# PMI_board.net
KiCad netlist of a schematic drawn in EAGLE
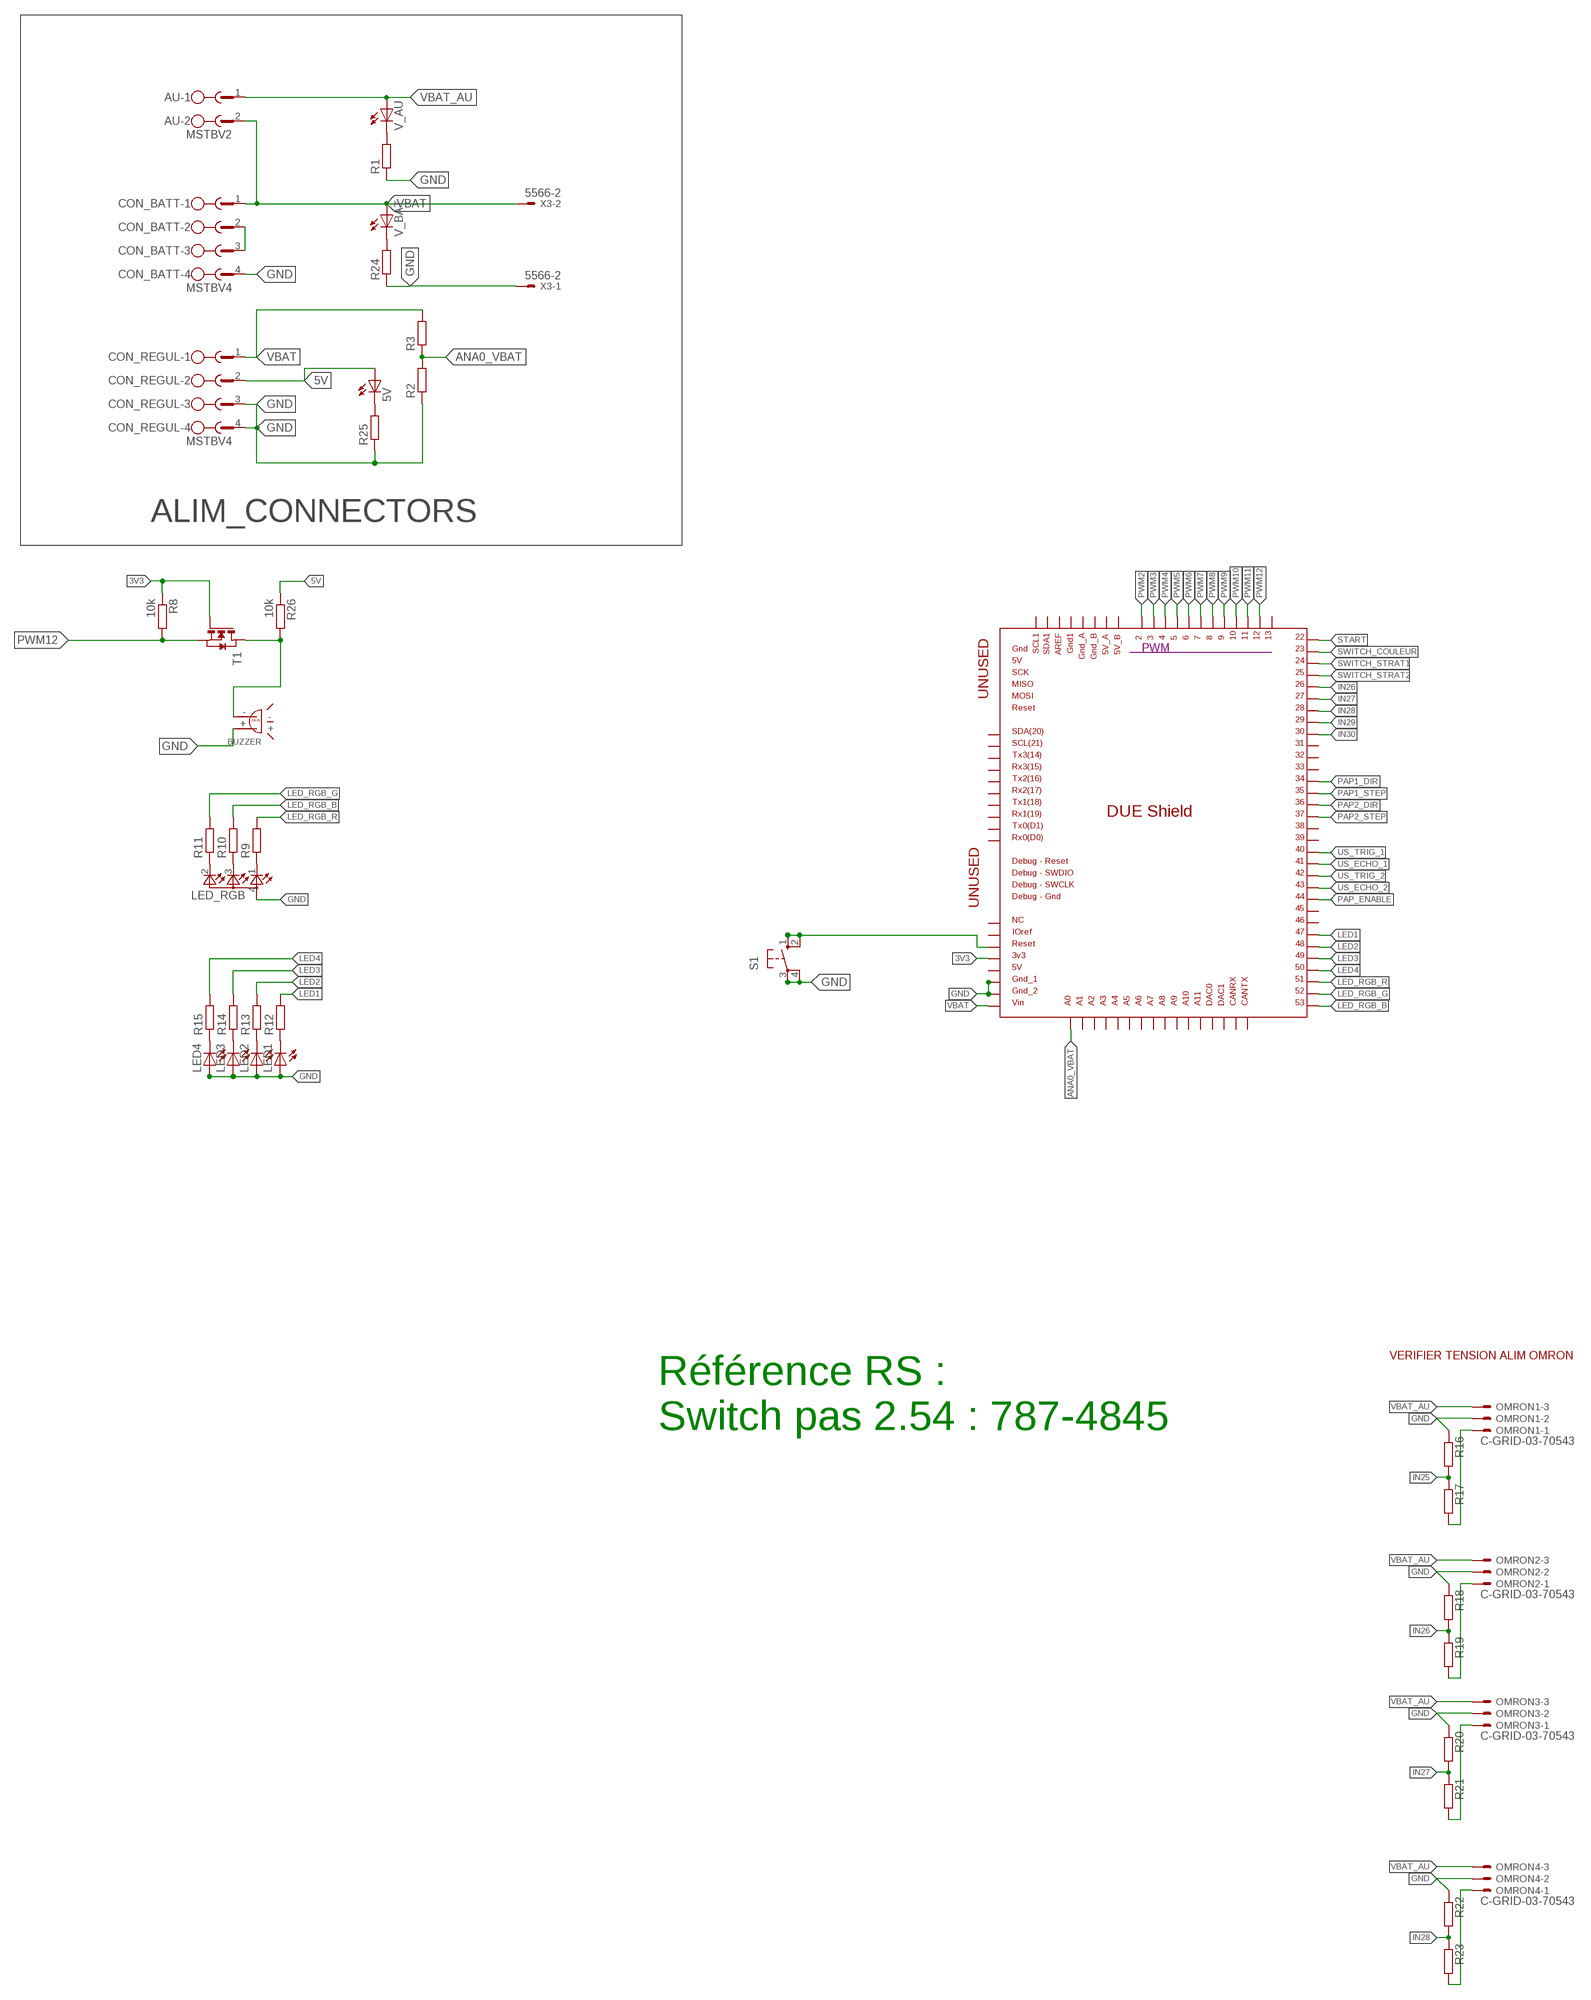
[diagram p0: schematic, sheet 1, part 1 of 2]
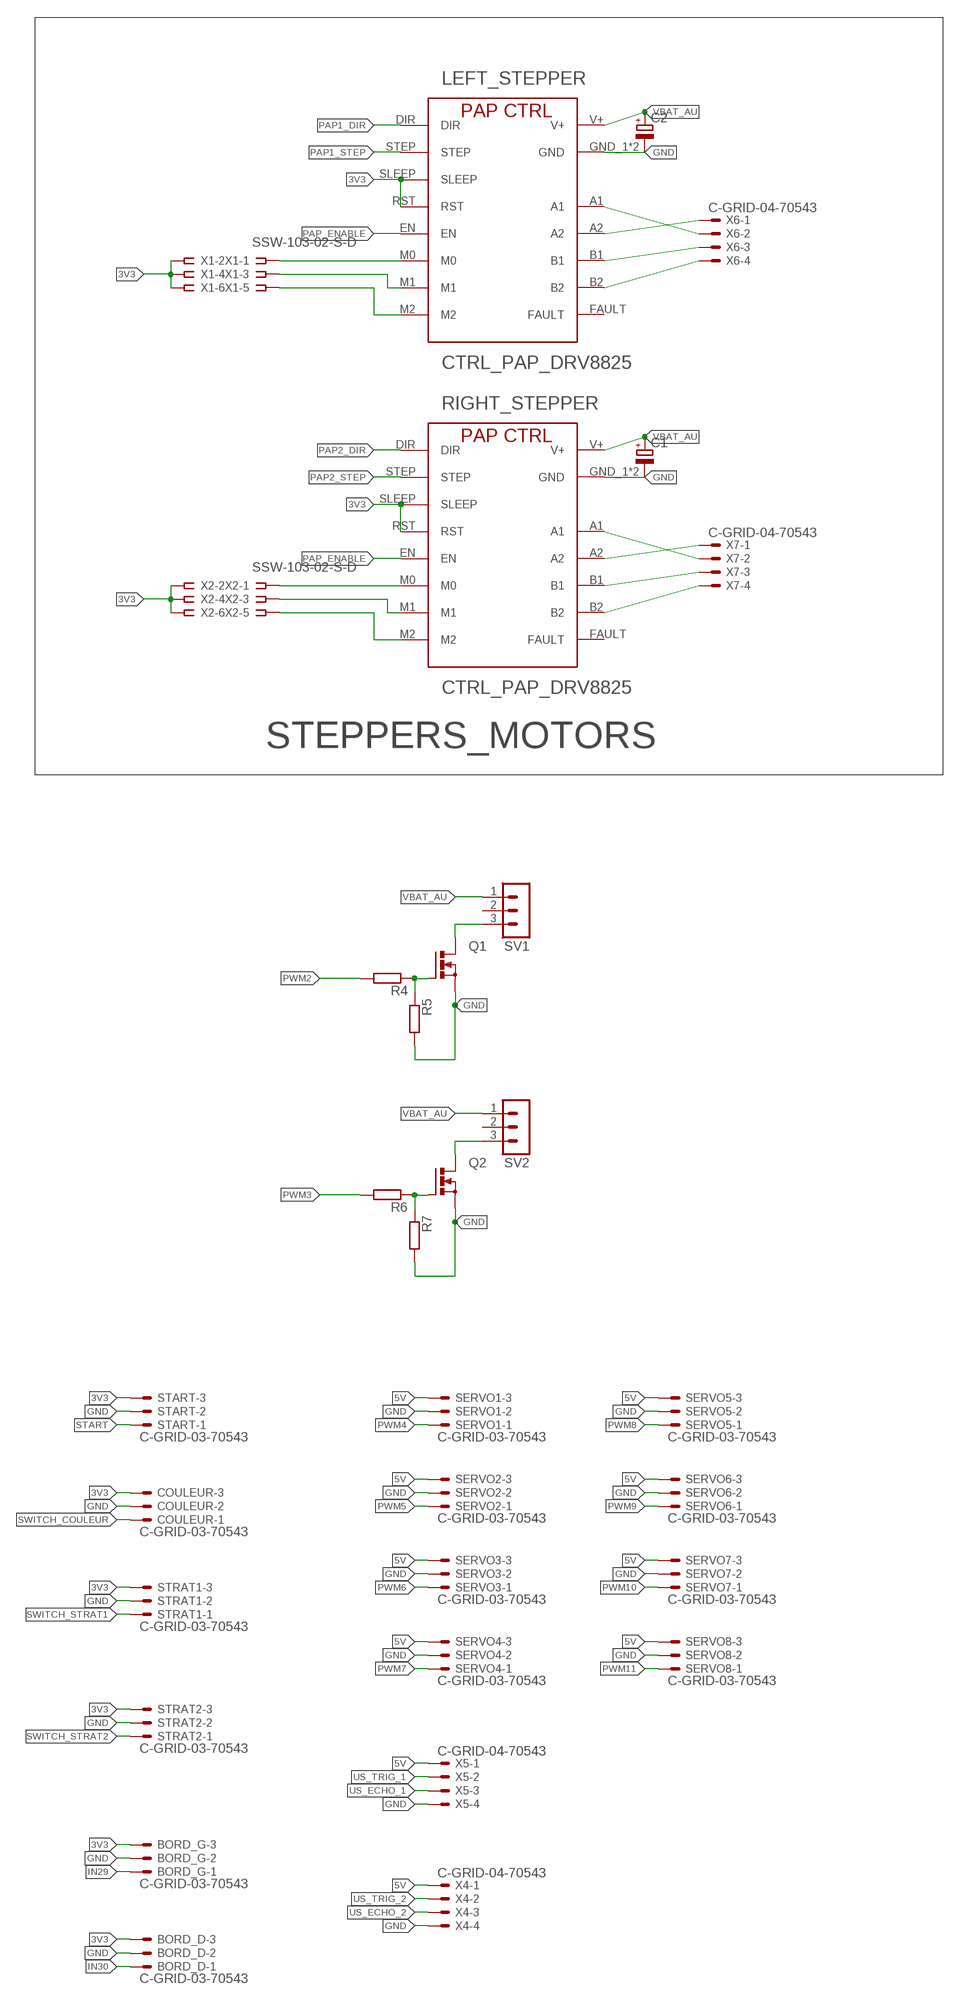
[diagram p1: schematic, sheet 1, part 2 of 2]

(export (version "E")
  (design (tool "Eeschema 10.0.6"))
  (components
    (comp (ref "5V")
      (value "LED5MM")
      (footprint "eagle-import:LED5MM")
      (libsource (lib "eagle-import") (part "LED5MM"))
    )
    (comp (ref "AU")
      (value "MSTBV2")
      (footprint "eagle-import:MSTBV2")
      (fields (field (name "MPN") "MSTBV 2,5/2-GF-5.08"))
      (libsource (lib "eagle-import") (part "MSTBV2"))
    )
    (comp (ref "BORD_D")
      (value "C-GRID-03-70543")
      (footprint "eagle-import:70543-03")
      (libsource (lib "eagle-import") (part "C-GRID-03-70543"))
    )
    (comp (ref "BORD_G")
      (value "C-GRID-03-70543")
      (footprint "eagle-import:70543-03")
      (libsource (lib "eagle-import") (part "C-GRID-03-70543"))
    )
    (comp (ref "BUZZER")
      (value "BUZZER")
      (footprint "eagle-import:BUZZER")
      (libsource (lib "eagle-import") (part "BUZZER"))
    )
    (comp (ref "C1")
      (value "CPOL-EUD")
      (footprint "eagle-import:PANASONIC_D")
      (libsource (lib "eagle-import") (part "CPOL-EUD"))
    )
    (comp (ref "C2")
      (value "CPOL-EUD")
      (footprint "eagle-import:PANASONIC_D")
      (libsource (lib "eagle-import") (part "CPOL-EUD"))
    )
    (comp (ref "CON_BATT")
      (value "MSTBV4")
      (footprint "eagle-import:MSTBV4")
      (fields (field (name "MPN") "MSTBV 2,5/4-GF-5.08"))
      (libsource (lib "eagle-import") (part "MSTBV4"))
    )
    (comp (ref "CON_REGUL")
      (value "MSTBV4")
      (footprint "eagle-import:MSTBV4")
      (fields (field (name "MPN") "MSTBV 2,5/4-GF-5.08"))
      (libsource (lib "eagle-import") (part "MSTBV4"))
    )
    (comp (ref "COULEUR")
      (value "C-GRID-03-70543")
      (footprint "eagle-import:70543-03")
      (libsource (lib "eagle-import") (part "C-GRID-03-70543"))
    )
    (comp (ref "LED1")
      (value "LED3MM")
      (footprint "eagle-import:LED3MM")
      (libsource (lib "eagle-import") (part "LED3MM"))
    )
    (comp (ref "LED2")
      (value "LED3MM")
      (footprint "eagle-import:LED3MM")
      (libsource (lib "eagle-import") (part "LED3MM"))
    )
    (comp (ref "LED3")
      (value "LED3MM")
      (footprint "eagle-import:LED3MM")
      (libsource (lib "eagle-import") (part "LED3MM"))
    )
    (comp (ref "LED4")
      (value "LED3MM")
      (footprint "eagle-import:LED3MM")
      (libsource (lib "eagle-import") (part "LED3MM"))
    )
    (comp (ref "LED_RGB")
      (value "TOPLED-3QPE_MAPPING")
      (footprint "eagle-import:P-LCC-4-3")
      (libsource (lib "eagle-import") (part "TOPLED-3QPE_MAPPING"))
    )
    (comp (ref "LEFT_STEPPER")
      (value "CTRL_PAP_DRV8825")
      (footprint "eagle-import:CTRL_PAP")
      (libsource (lib "eagle-import") (part "CTRL_PAP_DRV8825"))
    )
    (comp (ref "OMRON1")
      (value "C-GRID-03-70543")
      (footprint "eagle-import:70543-03")
      (libsource (lib "eagle-import") (part "C-GRID-03-70543"))
    )
    (comp (ref "OMRON2")
      (value "C-GRID-03-70543")
      (footprint "eagle-import:70543-03")
      (libsource (lib "eagle-import") (part "C-GRID-03-70543"))
    )
    (comp (ref "OMRON3")
      (value "C-GRID-03-70543")
      (footprint "eagle-import:70543-03")
      (libsource (lib "eagle-import") (part "C-GRID-03-70543"))
    )
    (comp (ref "OMRON4")
      (value "C-GRID-03-70543")
      (footprint "eagle-import:70543-03")
      (libsource (lib "eagle-import") (part "C-GRID-03-70543"))
    )
    (comp (ref "Q1")
      (value "PMOSFET_NTO220BV")
      (footprint "eagle-import:TO220BV")
      (libsource (lib "eagle-import") (part "PMOSFET_NTO220BV"))
    )
    (comp (ref "Q2")
      (value "PMOSFET_NTO220BV")
      (footprint "eagle-import:TO220BV")
      (libsource (lib "eagle-import") (part "PMOSFET_NTO220BV"))
    )
    (comp (ref "R1")
      (value "R-EU_M1206")
      (footprint "eagle-import:M1206")
      (libsource (lib "eagle-import") (part "R-EU_M1206"))
    )
    (comp (ref "R2")
      (value "R-EU_M1206")
      (footprint "eagle-import:M1206")
      (libsource (lib "eagle-import") (part "R-EU_M1206"))
    )
    (comp (ref "R3")
      (value "R-EU_M1206")
      (footprint "eagle-import:M1206")
      (libsource (lib "eagle-import") (part "R-EU_M1206"))
    )
    (comp (ref "R4")
      (value "R-EU_M1206")
      (footprint "eagle-import:M1206")
      (libsource (lib "eagle-import") (part "R-EU_M1206"))
    )
    (comp (ref "R5")
      (value "R-EU_M1206")
      (footprint "eagle-import:M1206")
      (libsource (lib "eagle-import") (part "R-EU_M1206"))
    )
    (comp (ref "R6")
      (value "R-EU_M1206")
      (footprint "eagle-import:M1206")
      (libsource (lib "eagle-import") (part "R-EU_M1206"))
    )
    (comp (ref "R7")
      (value "R-EU_M1206")
      (footprint "eagle-import:M1206")
      (libsource (lib "eagle-import") (part "R-EU_M1206"))
    )
    (comp (ref "R8")
      (value "10k")
      (footprint "eagle-import:M1206")
      (libsource (lib "eagle-import") (part "R-EU_M1206"))
    )
    (comp (ref "R9")
      (value "R-EU_M1206")
      (footprint "eagle-import:M1206")
      (libsource (lib "eagle-import") (part "R-EU_M1206"))
    )
    (comp (ref "R10")
      (value "R-EU_M1206")
      (footprint "eagle-import:M1206")
      (libsource (lib "eagle-import") (part "R-EU_M1206"))
    )
    (comp (ref "R11")
      (value "R-EU_M1206")
      (footprint "eagle-import:M1206")
      (libsource (lib "eagle-import") (part "R-EU_M1206"))
    )
    (comp (ref "R12")
      (value "R-EU_M1206")
      (footprint "eagle-import:M1206")
      (libsource (lib "eagle-import") (part "R-EU_M1206"))
    )
    (comp (ref "R13")
      (value "R-EU_M1206")
      (footprint "eagle-import:M1206")
      (libsource (lib "eagle-import") (part "R-EU_M1206"))
    )
    (comp (ref "R14")
      (value "R-EU_M1206")
      (footprint "eagle-import:M1206")
      (libsource (lib "eagle-import") (part "R-EU_M1206"))
    )
    (comp (ref "R15")
      (value "R-EU_M1206")
      (footprint "eagle-import:M1206")
      (libsource (lib "eagle-import") (part "R-EU_M1206"))
    )
    (comp (ref "R16")
      (value "R-EU_M1206")
      (footprint "eagle-import:M1206")
      (libsource (lib "eagle-import") (part "R-EU_M1206"))
    )
    (comp (ref "R17")
      (value "R-EU_M1206")
      (footprint "eagle-import:M1206")
      (libsource (lib "eagle-import") (part "R-EU_M1206"))
    )
    (comp (ref "R18")
      (value "R-EU_M1206")
      (footprint "eagle-import:M1206")
      (libsource (lib "eagle-import") (part "R-EU_M1206"))
    )
    (comp (ref "R19")
      (value "R-EU_M1206")
      (footprint "eagle-import:M1206")
      (libsource (lib "eagle-import") (part "R-EU_M1206"))
    )
    (comp (ref "R20")
      (value "R-EU_M1206")
      (footprint "eagle-import:M1206")
      (libsource (lib "eagle-import") (part "R-EU_M1206"))
    )
    (comp (ref "R21")
      (value "R-EU_M1206")
      (footprint "eagle-import:M1206")
      (libsource (lib "eagle-import") (part "R-EU_M1206"))
    )
    (comp (ref "R22")
      (value "R-EU_M1206")
      (footprint "eagle-import:M1206")
      (libsource (lib "eagle-import") (part "R-EU_M1206"))
    )
    (comp (ref "R23")
      (value "R-EU_M1206")
      (footprint "eagle-import:M1206")
      (libsource (lib "eagle-import") (part "R-EU_M1206"))
    )
    (comp (ref "R24")
      (value "R-EU_M1206")
      (footprint "eagle-import:M1206")
      (libsource (lib "eagle-import") (part "R-EU_M1206"))
    )
    (comp (ref "R25")
      (value "R-EU_M1206")
      (footprint "eagle-import:M1206")
      (libsource (lib "eagle-import") (part "R-EU_M1206"))
    )
    (comp (ref "R26")
      (value "10k")
      (footprint "eagle-import:M1206")
      (libsource (lib "eagle-import") (part "R-EU_M1206"))
    )
    (comp (ref "RIGHT_STEPPER")
      (value "CTRL_PAP_DRV8825")
      (footprint "eagle-import:CTRL_PAP")
      (libsource (lib "eagle-import") (part "CTRL_PAP_DRV8825"))
    )
    (comp (ref "S1")
      (value "10-XX")
      (footprint "eagle-import:B3F-10XX")
      (fields (field (name "MPN") "B3F-1000"))
      (libsource (lib "eagle-import") (part "10-XX"))
    )
    (comp (ref "SERVO1")
      (value "C-GRID-03-70543")
      (footprint "eagle-import:70543-03")
      (libsource (lib "eagle-import") (part "C-GRID-03-70543"))
    )
    (comp (ref "SERVO2")
      (value "C-GRID-03-70543")
      (footprint "eagle-import:70543-03")
      (libsource (lib "eagle-import") (part "C-GRID-03-70543"))
    )
    (comp (ref "SERVO3")
      (value "C-GRID-03-70543")
      (footprint "eagle-import:70543-03")
      (libsource (lib "eagle-import") (part "C-GRID-03-70543"))
    )
    (comp (ref "SERVO4")
      (value "C-GRID-03-70543")
      (footprint "eagle-import:70543-03")
      (libsource (lib "eagle-import") (part "C-GRID-03-70543"))
    )
    (comp (ref "SERVO5")
      (value "C-GRID-03-70543")
      (footprint "eagle-import:70543-03")
      (libsource (lib "eagle-import") (part "C-GRID-03-70543"))
    )
    (comp (ref "SERVO6")
      (value "C-GRID-03-70543")
      (footprint "eagle-import:70543-03")
      (libsource (lib "eagle-import") (part "C-GRID-03-70543"))
    )
    (comp (ref "SERVO7")
      (value "C-GRID-03-70543")
      (footprint "eagle-import:70543-03")
      (libsource (lib "eagle-import") (part "C-GRID-03-70543"))
    )
    (comp (ref "SERVO8")
      (value "C-GRID-03-70543")
      (footprint "eagle-import:70543-03")
      (libsource (lib "eagle-import") (part "C-GRID-03-70543"))
    )
    (comp (ref "START")
      (value "C-GRID-03-70543")
      (footprint "eagle-import:70543-03")
      (libsource (lib "eagle-import") (part "C-GRID-03-70543"))
    )
    (comp (ref "STRAT1")
      (value "C-GRID-03-70543")
      (footprint "eagle-import:70543-03")
      (libsource (lib "eagle-import") (part "C-GRID-03-70543"))
    )
    (comp (ref "STRAT2")
      (value "C-GRID-03-70543")
      (footprint "eagle-import:70543-03")
      (libsource (lib "eagle-import") (part "C-GRID-03-70543"))
    )
    (comp (ref "SV1")
      (value "MA03-1")
      (footprint "eagle-import:MA03-1")
      (libsource (lib "eagle-import") (part "MA03-1"))
    )
    (comp (ref "SV2")
      (value "MA03-1")
      (footprint "eagle-import:MA03-1")
      (libsource (lib "eagle-import") (part "MA03-1"))
    )
    (comp (ref "T1")
      (value "NMOSSOT23")
      (footprint "eagle-import:SOT-23")
      (libsource (lib "eagle-import") (part "NMOSSOT23"))
    )
    (comp (ref "U$1")
      (value "DUE(NORMAL)")
      (footprint "eagle-import:DUE(NORMAL)")
      (libsource (lib "eagle-import") (part "DUE(NORMAL)"))
    )
    (comp (ref "V_AU")
      (value "LED5MM")
      (footprint "eagle-import:LED5MM")
      (libsource (lib "eagle-import") (part "LED5MM"))
    )
    (comp (ref "V_BAT")
      (value "LED5MM")
      (footprint "eagle-import:LED5MM")
      (libsource (lib "eagle-import") (part "LED5MM"))
    )
    (comp (ref "X1")
      (value "SSW-103-02-S-D")
      (footprint "eagle-import:SSW-103-02-S-D")
      (libsource (lib "eagle-import") (part "SSW-103-02-S-D"))
    )
    (comp (ref "X2")
      (value "SSW-103-02-S-D")
      (footprint "eagle-import:SSW-103-02-S-D")
      (libsource (lib "eagle-import") (part "SSW-103-02-S-D"))
    )
    (comp (ref "X3")
      (value "5566-2")
      (footprint "eagle-import:5566-2")
      (libsource (lib "eagle-import") (part "5566-2"))
    )
    (comp (ref "X4")
      (value "C-GRID-04-70543")
      (footprint "eagle-import:70543-04")
      (libsource (lib "eagle-import") (part "C-GRID-04-70543"))
    )
    (comp (ref "X5")
      (value "C-GRID-04-70543")
      (footprint "eagle-import:70543-04")
      (libsource (lib "eagle-import") (part "C-GRID-04-70543"))
    )
    (comp (ref "X6")
      (value "C-GRID-04-70543")
      (footprint "eagle-import:70543-04")
      (libsource (lib "eagle-import") (part "C-GRID-04-70543"))
    )
    (comp (ref "X7")
      (value "C-GRID-04-70543")
      (footprint "eagle-import:70543-04")
      (libsource (lib "eagle-import") (part "C-GRID-04-70543"))
    )
  )
  (nets
    (net (code "1") (name "3V3") (class "Default")
      (node (ref "BORD_D") (pin "3") (pinfunction "S_3") (pintype "passive"))
      (node (ref "BORD_G") (pin "3") (pinfunction "S_3") (pintype "passive"))
      (node (ref "COULEUR") (pin "3") (pinfunction "S_3") (pintype "passive"))
      (node (ref "LEFT_STEPPER") (pin "RST") (pinfunction "RST_RST") (pintype "bidirectional"))
      (node (ref "LEFT_STEPPER") (pin "SLEEP") (pinfunction "SLEEP_SLEEP") (pintype "bidirectional"))
      (node (ref "R8") (pin "1") (pinfunction "1_1") (pintype "passive"))
      (node (ref "RIGHT_STEPPER") (pin "RST") (pinfunction "RST_RST") (pintype "bidirectional"))
      (node (ref "RIGHT_STEPPER") (pin "SLEEP") (pinfunction "SLEEP_SLEEP") (pintype "bidirectional"))
      (node (ref "START") (pin "3") (pinfunction "S_3") (pintype "passive"))
      (node (ref "STRAT1") (pin "3") (pinfunction "S_3") (pintype "passive"))
      (node (ref "STRAT2") (pin "3") (pinfunction "S_3") (pintype "passive"))
      (node (ref "T1") (pin "3") (pinfunction "G_3") (pintype "passive"))
      (node (ref "U$1") (pin "3V3") (pinfunction "3V3_3V3") (pintype "bidirectional"))
      (node (ref "X1") (pin "2") (pinfunction "1_2") (pintype "passive"))
      (node (ref "X1") (pin "4") (pinfunction "1_4") (pintype "passive"))
      (node (ref "X1") (pin "6") (pinfunction "1_6") (pintype "passive"))
      (node (ref "X2") (pin "2") (pinfunction "1_2") (pintype "passive"))
      (node (ref "X2") (pin "4") (pinfunction "1_4") (pintype "passive"))
      (node (ref "X2") (pin "6") (pinfunction "1_6") (pintype "passive"))
    )
    (net (code "2") (name "5V") (class "Default")
      (node (ref "5V") (pin "A") (pinfunction "A_A") (pintype "passive"))
      (node (ref "CON_REGUL") (pin "2") (pinfunction "1_2") (pintype "passive"))
      (node (ref "R26") (pin "1") (pinfunction "1_1") (pintype "passive"))
      (node (ref "SERVO1") (pin "3") (pinfunction "S_3") (pintype "passive"))
      (node (ref "SERVO2") (pin "3") (pinfunction "S_3") (pintype "passive"))
      (node (ref "SERVO3") (pin "3") (pinfunction "S_3") (pintype "passive"))
      (node (ref "SERVO4") (pin "3") (pinfunction "S_3") (pintype "passive"))
      (node (ref "SERVO5") (pin "3") (pinfunction "S_3") (pintype "passive"))
      (node (ref "SERVO6") (pin "3") (pinfunction "S_3") (pintype "passive"))
      (node (ref "SERVO7") (pin "3") (pinfunction "S_3") (pintype "passive"))
      (node (ref "SERVO8") (pin "3") (pinfunction "S_3") (pintype "passive"))
      (node (ref "X4") (pin "1") (pinfunction "S_1") (pintype "passive"))
      (node (ref "X5") (pin "1") (pinfunction "S_1") (pintype "passive"))
    )
    (net (code "3") (name "ANA0_VBAT") (class "Default")
      (node (ref "R2") (pin "2") (pinfunction "2_2") (pintype "passive"))
      (node (ref "R3") (pin "1") (pinfunction "1_1") (pintype "passive"))
      (node (ref "U$1") (pin "A0") (pinfunction "A0_A0") (pintype "bidirectional"))
    )
    (net (code "4") (name "GND") (class "Default")
      (node (ref "BORD_D") (pin "2") (pinfunction "S_2") (pintype "passive"))
      (node (ref "BORD_G") (pin "2") (pinfunction "S_2") (pintype "passive"))
      (node (ref "BUZZER") (pin "+") (pinfunction "+_+") (pintype "bidirectional"))
      (node (ref "C1") (pin "-") (pinfunction "-_-") (pintype "passive"))
      (node (ref "C2") (pin "-") (pinfunction "-_-") (pintype "passive"))
      (node (ref "CON_BATT") (pin "4") (pinfunction "1_4") (pintype "passive"))
      (node (ref "CON_REGUL") (pin "3") (pinfunction "1_3") (pintype "passive"))
      (node (ref "CON_REGUL") (pin "4") (pinfunction "1_4") (pintype "passive"))
      (node (ref "COULEUR") (pin "2") (pinfunction "S_2") (pintype "passive"))
      (node (ref "LED1") (pin "A") (pinfunction "A_A") (pintype "passive"))
      (node (ref "LED2") (pin "A") (pinfunction "A_A") (pintype "passive"))
      (node (ref "LED3") (pin "A") (pinfunction "A_A") (pintype "passive"))
      (node (ref "LED4") (pin "A") (pinfunction "A_A") (pintype "passive"))
      (node (ref "LED_RGB") (pin "4") (pinfunction "A2_4") (pintype "passive"))
      (node (ref "LEFT_STEPPER") (pin "GND_1") (pinfunction "GND_GND_1") (pintype "bidirectional"))
      (node (ref "LEFT_STEPPER") (pin "GND_2") (pinfunction "GND_GND_2") (pintype "bidirectional"))
      (node (ref "OMRON1") (pin "2") (pinfunction "S_2") (pintype "passive"))
      (node (ref "OMRON2") (pin "2") (pinfunction "S_2") (pintype "passive"))
      (node (ref "OMRON3") (pin "2") (pinfunction "S_2") (pintype "passive"))
      (node (ref "OMRON4") (pin "2") (pinfunction "S_2") (pintype "passive"))
      (node (ref "Q1") (pin "S") (pinfunction "S_S") (pintype "passive"))
      (node (ref "Q2") (pin "S") (pinfunction "S_S") (pintype "passive"))
      (node (ref "R1") (pin "1") (pinfunction "1_1") (pintype "passive"))
      (node (ref "R16") (pin "1") (pinfunction "1_1") (pintype "passive"))
      (node (ref "R18") (pin "1") (pinfunction "1_1") (pintype "passive"))
      (node (ref "R2") (pin "1") (pinfunction "1_1") (pintype "passive"))
      (node (ref "R20") (pin "1") (pinfunction "1_1") (pintype "passive"))
      (node (ref "R22") (pin "1") (pinfunction "1_1") (pintype "passive"))
      (node (ref "R24") (pin "1") (pinfunction "1_1") (pintype "passive"))
      (node (ref "R25") (pin "1") (pinfunction "1_1") (pintype "passive"))
      (node (ref "R5") (pin "2") (pinfunction "2_2") (pintype "passive"))
      (node (ref "R7") (pin "2") (pinfunction "2_2") (pintype "passive"))
      (node (ref "RIGHT_STEPPER") (pin "GND_1") (pinfunction "GND_GND_1") (pintype "bidirectional"))
      (node (ref "RIGHT_STEPPER") (pin "GND_2") (pinfunction "GND_GND_2") (pintype "bidirectional"))
      (node (ref "S1") (pin "3") (pinfunction "P_3") (pintype "passive"))
      (node (ref "S1") (pin "4") (pinfunction "P1_4") (pintype "passive"))
      (node (ref "SERVO1") (pin "2") (pinfunction "S_2") (pintype "passive"))
      (node (ref "SERVO2") (pin "2") (pinfunction "S_2") (pintype "passive"))
      (node (ref "SERVO3") (pin "2") (pinfunction "S_2") (pintype "passive"))
      (node (ref "SERVO4") (pin "2") (pinfunction "S_2") (pintype "passive"))
      (node (ref "SERVO5") (pin "2") (pinfunction "S_2") (pintype "passive"))
      (node (ref "SERVO6") (pin "2") (pinfunction "S_2") (pintype "passive"))
      (node (ref "SERVO7") (pin "2") (pinfunction "S_2") (pintype "passive"))
      (node (ref "SERVO8") (pin "2") (pinfunction "S_2") (pintype "passive"))
      (node (ref "START") (pin "2") (pinfunction "S_2") (pintype "passive"))
      (node (ref "STRAT1") (pin "2") (pinfunction "S_2") (pintype "passive"))
      (node (ref "STRAT2") (pin "2") (pinfunction "S_2") (pintype "passive"))
      (node (ref "U$1") (pin "GND_1") (pinfunction "GND_1_GND_1") (pintype "bidirectional"))
      (node (ref "U$1") (pin "GND_2") (pinfunction "GND_2_GND_2") (pintype "bidirectional"))
      (node (ref "X3") (pin "1") (pinfunction "S_1") (pintype "passive"))
      (node (ref "X4") (pin "4") (pinfunction "S_4") (pintype "passive"))
      (node (ref "X5") (pin "4") (pinfunction "S_4") (pintype "passive"))
    )
    (net (code "5") (name "IN25") (class "Default")
      (node (ref "R16") (pin "2") (pinfunction "2_2") (pintype "passive"))
      (node (ref "R17") (pin "1") (pinfunction "1_1") (pintype "passive"))
    )
    (net (code "6") (name "IN26") (class "Default")
      (node (ref "R18") (pin "2") (pinfunction "2_2") (pintype "passive"))
      (node (ref "R19") (pin "1") (pinfunction "1_1") (pintype "passive"))
      (node (ref "U$1") (pin "26") (pinfunction "26_26") (pintype "bidirectional"))
    )
    (net (code "7") (name "IN27") (class "Default")
      (node (ref "R20") (pin "2") (pinfunction "2_2") (pintype "passive"))
      (node (ref "R21") (pin "1") (pinfunction "1_1") (pintype "passive"))
      (node (ref "U$1") (pin "27") (pinfunction "27_27") (pintype "bidirectional"))
    )
    (net (code "8") (name "IN28") (class "Default")
      (node (ref "R22") (pin "2") (pinfunction "2_2") (pintype "passive"))
      (node (ref "R23") (pin "1") (pinfunction "1_1") (pintype "passive"))
      (node (ref "U$1") (pin "28") (pinfunction "28_28") (pintype "bidirectional"))
    )
    (net (code "9") (name "IN29") (class "Default")
      (node (ref "BORD_G") (pin "1") (pinfunction "S_1") (pintype "passive"))
      (node (ref "U$1") (pin "29") (pinfunction "29_29") (pintype "bidirectional"))
    )
    (net (code "10") (name "IN30") (class "Default")
      (node (ref "BORD_D") (pin "1") (pinfunction "S_1") (pintype "passive"))
      (node (ref "U$1") (pin "30") (pinfunction "30_30") (pintype "bidirectional"))
    )
    (net (code "11") (name "LED1") (class "Default")
      (node (ref "R12") (pin "2") (pinfunction "2_2") (pintype "passive"))
      (node (ref "U$1") (pin "47") (pinfunction "47_47") (pintype "bidirectional"))
    )
    (net (code "12") (name "LED2") (class "Default")
      (node (ref "R13") (pin "2") (pinfunction "2_2") (pintype "passive"))
      (node (ref "U$1") (pin "48") (pinfunction "48_48") (pintype "bidirectional"))
    )
    (net (code "13") (name "LED3") (class "Default")
      (node (ref "R14") (pin "2") (pinfunction "2_2") (pintype "passive"))
      (node (ref "U$1") (pin "49") (pinfunction "49_49") (pintype "bidirectional"))
    )
    (net (code "14") (name "LED4") (class "Default")
      (node (ref "R15") (pin "2") (pinfunction "2_2") (pintype "passive"))
      (node (ref "U$1") (pin "50") (pinfunction "50_50") (pintype "bidirectional"))
    )
    (net (code "15") (name "LED_RGB_B") (class "Default")
      (node (ref "R10") (pin "2") (pinfunction "2_2") (pintype "passive"))
      (node (ref "U$1") (pin "53") (pinfunction "53_53") (pintype "bidirectional"))
    )
    (net (code "16") (name "LED_RGB_G") (class "Default")
      (node (ref "R11") (pin "2") (pinfunction "2_2") (pintype "passive"))
      (node (ref "U$1") (pin "52") (pinfunction "52_52") (pintype "bidirectional"))
    )
    (net (code "17") (name "LED_RGB_R") (class "Default")
      (node (ref "R9") (pin "2") (pinfunction "2_2") (pintype "passive"))
      (node (ref "U$1") (pin "51") (pinfunction "51_51") (pintype "bidirectional"))
    )
    (net (code "18") (name "Net-(5V-C)") (class "Default")
      (node (ref "5V") (pin "K") (pinfunction "C_K") (pintype "passive"))
      (node (ref "R25") (pin "2") (pinfunction "2_2") (pintype "passive"))
    )
    (net (code "19") (name "Net-(CON_BATTB-1)") (class "Default")
      (node (ref "CON_BATT") (pin "2") (pinfunction "1_2") (pintype "passive"))
      (node (ref "CON_BATT") (pin "3") (pinfunction "1_3") (pintype "passive"))
    )
    (net (code "20") (name "Net-(LED1-C)") (class "Default")
      (node (ref "LED1") (pin "K") (pinfunction "C_K") (pintype "passive"))
      (node (ref "R12") (pin "1") (pinfunction "1_1") (pintype "passive"))
    )
    (net (code "21") (name "Net-(LED2-C)") (class "Default")
      (node (ref "LED2") (pin "K") (pinfunction "C_K") (pintype "passive"))
      (node (ref "R13") (pin "1") (pinfunction "1_1") (pintype "passive"))
    )
    (net (code "22") (name "Net-(LED3-C)") (class "Default")
      (node (ref "LED3") (pin "K") (pinfunction "C_K") (pintype "passive"))
      (node (ref "R14") (pin "1") (pinfunction "1_1") (pintype "passive"))
    )
    (net (code "23") (name "Net-(LED4-C)") (class "Default")
      (node (ref "LED4") (pin "K") (pinfunction "C_K") (pintype "passive"))
      (node (ref "R15") (pin "1") (pinfunction "1_1") (pintype "passive"))
    )
    (net (code "24") (name "Net-(LED_RGB-CBLUE)") (class "Default")
      (node (ref "LED_RGB") (pin "3") (pinfunction "CBLUE_3") (pintype "passive"))
      (node (ref "R10") (pin "1") (pinfunction "1_1") (pintype "passive"))
    )
    (net (code "25") (name "Net-(LED_RGB-CGREEN)") (class "Default")
      (node (ref "LED_RGB") (pin "2") (pinfunction "CGREEN_2") (pintype "passive"))
      (node (ref "R11") (pin "1") (pinfunction "1_1") (pintype "passive"))
    )
    (net (code "26") (name "Net-(LED_RGB-CRED)") (class "Default")
      (node (ref "LED_RGB") (pin "1") (pinfunction "CRED_1") (pintype "passive"))
      (node (ref "R9") (pin "1") (pinfunction "1_1") (pintype "passive"))
    )
    (net (code "27") (name "Net-(LEFT_STEPPER-PadM0)") (class "Default")
      (node (ref "LEFT_STEPPER") (pin "M0") (pinfunction "M0_M0") (pintype "bidirectional"))
      (node (ref "X1") (pin "1") (pinfunction "1_1") (pintype "passive"))
    )
    (net (code "28") (name "Net-(OMRON1A-S)") (class "Default")
      (node (ref "OMRON1") (pin "1") (pinfunction "S_1") (pintype "passive"))
      (node (ref "R17") (pin "2") (pinfunction "2_2") (pintype "passive"))
    )
    (net (code "29") (name "Net-(OMRON2A-S)") (class "Default")
      (node (ref "OMRON2") (pin "1") (pinfunction "S_1") (pintype "passive"))
      (node (ref "R19") (pin "2") (pinfunction "2_2") (pintype "passive"))
    )
    (net (code "30") (name "Net-(OMRON3A-S)") (class "Default")
      (node (ref "OMRON3") (pin "1") (pinfunction "S_1") (pintype "passive"))
      (node (ref "R21") (pin "2") (pinfunction "2_2") (pintype "passive"))
    )
    (net (code "31") (name "Net-(OMRON4A-S)") (class "Default")
      (node (ref "OMRON4") (pin "1") (pinfunction "S_1") (pintype "passive"))
      (node (ref "R23") (pin "2") (pinfunction "2_2") (pintype "passive"))
    )
    (net (code "32") (name "Net-(Q1-PadD)") (class "Default")
      (node (ref "Q1") (pin "D") (pinfunction "D_D") (pintype "passive"))
      (node (ref "SV1") (pin "3") (pinfunction "3_3") (pintype "passive"))
    )
    (net (code "33") (name "Net-(Q1-PadG)") (class "Default")
      (node (ref "Q1") (pin "G") (pinfunction "G_G") (pintype "passive"))
      (node (ref "R4") (pin "1") (pinfunction "1_1") (pintype "passive"))
      (node (ref "R5") (pin "1") (pinfunction "1_1") (pintype "passive"))
    )
    (net (code "34") (name "Net-(Q2-PadD)") (class "Default")
      (node (ref "Q2") (pin "D") (pinfunction "D_D") (pintype "passive"))
      (node (ref "SV2") (pin "3") (pinfunction "3_3") (pintype "passive"))
    )
    (net (code "35") (name "Net-(Q2-PadG)") (class "Default")
      (node (ref "Q2") (pin "G") (pinfunction "G_G") (pintype "passive"))
      (node (ref "R6") (pin "1") (pinfunction "1_1") (pintype "passive"))
      (node (ref "R7") (pin "1") (pinfunction "1_1") (pintype "passive"))
    )
    (net (code "36") (name "Net-(RIGHT_STEPPER-PadM0)") (class "Default")
      (node (ref "RIGHT_STEPPER") (pin "M0") (pinfunction "M0_M0") (pintype "bidirectional"))
      (node (ref "X2") (pin "1") (pinfunction "1_1") (pintype "passive"))
    )
    (net (code "37") (name "Net-(S1-S)") (class "Default")
      (node (ref "S1") (pin "1") (pinfunction "S_1") (pintype "passive"))
      (node (ref "S1") (pin "2") (pinfunction "S1_2") (pintype "passive"))
      (node (ref "U$1") (pin "RESET") (pinfunction "RESET_RESET") (pintype "bidirectional"))
    )
    (net (code "38") (name "Net-(T1-D)") (class "Default")
      (node (ref "BUZZER") (pin "-") (pinfunction "-_-") (pintype "bidirectional"))
      (node (ref "R26") (pin "2") (pinfunction "2_2") (pintype "passive"))
      (node (ref "T1") (pin "1") (pinfunction "D_1") (pintype "passive"))
    )
    (net (code "39") (name "Net-(V_AU-C)") (class "Default")
      (node (ref "R1") (pin "2") (pinfunction "2_2") (pintype "passive"))
      (node (ref "V_AU") (pin "K") (pinfunction "C_K") (pintype "passive"))
    )
    (net (code "40") (name "Net-(V_BAT-C)") (class "Default")
      (node (ref "R24") (pin "2") (pinfunction "2_2") (pintype "passive"))
      (node (ref "V_BAT") (pin "K") (pinfunction "C_K") (pintype "passive"))
    )
    (net (code "41") (name "Net-(X1C-1)") (class "Default")
      (node (ref "LEFT_STEPPER") (pin "M1") (pinfunction "M1_M1") (pintype "bidirectional"))
      (node (ref "X1") (pin "3") (pinfunction "1_3") (pintype "passive"))
    )
    (net (code "42") (name "Net-(X1E-1)") (class "Default")
      (node (ref "LEFT_STEPPER") (pin "M2") (pinfunction "M2_M2") (pintype "bidirectional"))
      (node (ref "X1") (pin "5") (pinfunction "1_5") (pintype "passive"))
    )
    (net (code "43") (name "Net-(X2C-1)") (class "Default")
      (node (ref "RIGHT_STEPPER") (pin "M1") (pinfunction "M1_M1") (pintype "bidirectional"))
      (node (ref "X2") (pin "3") (pinfunction "1_3") (pintype "passive"))
    )
    (net (code "44") (name "Net-(X2E-1)") (class "Default")
      (node (ref "RIGHT_STEPPER") (pin "M2") (pinfunction "M2_M2") (pintype "bidirectional"))
      (node (ref "X2") (pin "5") (pinfunction "1_5") (pintype "passive"))
    )
    (net (code "45") (name "Net-(X6A-S)") (class "Default")
      (node (ref "LEFT_STEPPER") (pin "A2") (pinfunction "A2_A2") (pintype "bidirectional"))
      (node (ref "X6") (pin "1") (pinfunction "S_1") (pintype "passive"))
    )
    (net (code "46") (name "Net-(X6B-S)") (class "Default")
      (node (ref "LEFT_STEPPER") (pin "A1") (pinfunction "A1_A1") (pintype "bidirectional"))
      (node (ref "X6") (pin "2") (pinfunction "S_2") (pintype "passive"))
    )
    (net (code "47") (name "Net-(X6C-S)") (class "Default")
      (node (ref "LEFT_STEPPER") (pin "B1") (pinfunction "B1_B1") (pintype "bidirectional"))
      (node (ref "X6") (pin "3") (pinfunction "S_3") (pintype "passive"))
    )
    (net (code "48") (name "Net-(X6D-S)") (class "Default")
      (node (ref "LEFT_STEPPER") (pin "B2") (pinfunction "B2_B2") (pintype "bidirectional"))
      (node (ref "X6") (pin "4") (pinfunction "S_4") (pintype "passive"))
    )
    (net (code "49") (name "Net-(X7A-S)") (class "Default")
      (node (ref "RIGHT_STEPPER") (pin "A2") (pinfunction "A2_A2") (pintype "bidirectional"))
      (node (ref "X7") (pin "1") (pinfunction "S_1") (pintype "passive"))
    )
    (net (code "50") (name "Net-(X7B-S)") (class "Default")
      (node (ref "RIGHT_STEPPER") (pin "A1") (pinfunction "A1_A1") (pintype "bidirectional"))
      (node (ref "X7") (pin "2") (pinfunction "S_2") (pintype "passive"))
    )
    (net (code "51") (name "Net-(X7C-S)") (class "Default")
      (node (ref "RIGHT_STEPPER") (pin "B1") (pinfunction "B1_B1") (pintype "bidirectional"))
      (node (ref "X7") (pin "3") (pinfunction "S_3") (pintype "passive"))
    )
    (net (code "52") (name "Net-(X7D-S)") (class "Default")
      (node (ref "RIGHT_STEPPER") (pin "B2") (pinfunction "B2_B2") (pintype "bidirectional"))
      (node (ref "X7") (pin "4") (pinfunction "S_4") (pintype "passive"))
    )
    (net (code "53") (name "PAP1_DIR") (class "Default")
      (node (ref "LEFT_STEPPER") (pin "DIR") (pinfunction "DIR_DIR") (pintype "bidirectional"))
      (node (ref "U$1") (pin "34") (pinfunction "34_34") (pintype "bidirectional"))
    )
    (net (code "54") (name "PAP1_STEP") (class "Default")
      (node (ref "LEFT_STEPPER") (pin "STEP") (pinfunction "STEP_STEP") (pintype "bidirectional"))
      (node (ref "U$1") (pin "35") (pinfunction "35_35") (pintype "bidirectional"))
    )
    (net (code "55") (name "PAP2_DIR") (class "Default")
      (node (ref "RIGHT_STEPPER") (pin "DIR") (pinfunction "DIR_DIR") (pintype "bidirectional"))
      (node (ref "U$1") (pin "36") (pinfunction "36_36") (pintype "bidirectional"))
    )
    (net (code "56") (name "PAP2_STEP") (class "Default")
      (node (ref "RIGHT_STEPPER") (pin "STEP") (pinfunction "STEP_STEP") (pintype "bidirectional"))
      (node (ref "U$1") (pin "37") (pinfunction "37_37") (pintype "bidirectional"))
    )
    (net (code "57") (name "PAP_ENABLE") (class "Default")
      (node (ref "LEFT_STEPPER") (pin "EN") (pinfunction "EN_EN") (pintype "bidirectional"))
      (node (ref "RIGHT_STEPPER") (pin "EN") (pinfunction "EN_EN") (pintype "bidirectional"))
      (node (ref "U$1") (pin "44") (pinfunction "44_44") (pintype "bidirectional"))
    )
    (net (code "58") (name "PWM2") (class "Default")
      (node (ref "R4") (pin "2") (pinfunction "2_2") (pintype "passive"))
      (node (ref "U$1") (pin "2") (pinfunction "2_2") (pintype "bidirectional"))
    )
    (net (code "59") (name "PWM3") (class "Default")
      (node (ref "R6") (pin "2") (pinfunction "2_2") (pintype "passive"))
      (node (ref "U$1") (pin "3") (pinfunction "3_3") (pintype "bidirectional"))
    )
    (net (code "60") (name "PWM4") (class "Default")
      (node (ref "SERVO1") (pin "1") (pinfunction "S_1") (pintype "passive"))
      (node (ref "U$1") (pin "4") (pinfunction "4_4") (pintype "bidirectional"))
    )
    (net (code "61") (name "PWM5") (class "Default")
      (node (ref "SERVO2") (pin "1") (pinfunction "S_1") (pintype "passive"))
      (node (ref "U$1") (pin "5") (pinfunction "5_5") (pintype "bidirectional"))
    )
    (net (code "62") (name "PWM6") (class "Default")
      (node (ref "SERVO3") (pin "1") (pinfunction "S_1") (pintype "passive"))
      (node (ref "U$1") (pin "6") (pinfunction "6_6") (pintype "bidirectional"))
    )
    (net (code "63") (name "PWM7") (class "Default")
      (node (ref "SERVO4") (pin "1") (pinfunction "S_1") (pintype "passive"))
      (node (ref "U$1") (pin "7") (pinfunction "7_7") (pintype "bidirectional"))
    )
    (net (code "64") (name "PWM8") (class "Default")
      (node (ref "SERVO5") (pin "1") (pinfunction "S_1") (pintype "passive"))
      (node (ref "U$1") (pin "8") (pinfunction "8_8") (pintype "bidirectional"))
    )
    (net (code "65") (name "PWM9") (class "Default")
      (node (ref "SERVO6") (pin "1") (pinfunction "S_1") (pintype "passive"))
      (node (ref "U$1") (pin "9") (pinfunction "9_9") (pintype "bidirectional"))
    )
    (net (code "66") (name "PWM10") (class "Default")
      (node (ref "SERVO7") (pin "1") (pinfunction "S_1") (pintype "passive"))
      (node (ref "U$1") (pin "10") (pinfunction "10_10") (pintype "bidirectional"))
    )
    (net (code "67") (name "PWM11") (class "Default")
      (node (ref "SERVO8") (pin "1") (pinfunction "S_1") (pintype "passive"))
      (node (ref "U$1") (pin "11") (pinfunction "11_11") (pintype "bidirectional"))
    )
    (net (code "68") (name "PWM12") (class "Default")
      (node (ref "R8") (pin "2") (pinfunction "2_2") (pintype "passive"))
      (node (ref "T1") (pin "2") (pinfunction "S_2") (pintype "passive"))
      (node (ref "U$1") (pin "12") (pinfunction "12_12") (pintype "bidirectional"))
    )
    (net (code "69") (name "START") (class "Default")
      (node (ref "START") (pin "1") (pinfunction "S_1") (pintype "passive"))
      (node (ref "U$1") (pin "22") (pinfunction "22_22") (pintype "bidirectional"))
    )
    (net (code "70") (name "SWITCH_COULEUR") (class "Default")
      (node (ref "COULEUR") (pin "1") (pinfunction "S_1") (pintype "passive"))
      (node (ref "U$1") (pin "23") (pinfunction "23_23") (pintype "bidirectional"))
    )
    (net (code "71") (name "SWITCH_STRAT1") (class "Default")
      (node (ref "STRAT1") (pin "1") (pinfunction "S_1") (pintype "passive"))
      (node (ref "U$1") (pin "24") (pinfunction "24_24") (pintype "bidirectional"))
    )
    (net (code "72") (name "SWITCH_STRAT2") (class "Default")
      (node (ref "STRAT2") (pin "1") (pinfunction "S_1") (pintype "passive"))
      (node (ref "U$1") (pin "25") (pinfunction "25_25") (pintype "bidirectional"))
    )
    (net (code "73") (name "US_ECHO_1") (class "Default")
      (node (ref "U$1") (pin "41") (pinfunction "41_41") (pintype "bidirectional"))
      (node (ref "X5") (pin "3") (pinfunction "S_3") (pintype "passive"))
    )
    (net (code "74") (name "US_ECHO_2") (class "Default")
      (node (ref "U$1") (pin "43") (pinfunction "43_43") (pintype "bidirectional"))
      (node (ref "X4") (pin "3") (pinfunction "S_3") (pintype "passive"))
    )
    (net (code "75") (name "US_TRIG_1") (class "Default")
      (node (ref "U$1") (pin "40") (pinfunction "40_40") (pintype "bidirectional"))
      (node (ref "X5") (pin "2") (pinfunction "S_2") (pintype "passive"))
    )
    (net (code "76") (name "US_TRIG_2") (class "Default")
      (node (ref "U$1") (pin "42") (pinfunction "42_42") (pintype "bidirectional"))
      (node (ref "X4") (pin "2") (pinfunction "S_2") (pintype "passive"))
    )
    (net (code "77") (name "VBAT") (class "Default")
      (node (ref "AU") (pin "2") (pinfunction "1_2") (pintype "passive"))
      (node (ref "CON_BATT") (pin "1") (pinfunction "1_1") (pintype "passive"))
      (node (ref "CON_REGUL") (pin "1") (pinfunction "1_1") (pintype "passive"))
      (node (ref "R3") (pin "2") (pinfunction "2_2") (pintype "passive"))
      (node (ref "U$1") (pin "VIN") (pinfunction "VIN_VIN") (pintype "bidirectional"))
      (node (ref "V_BAT") (pin "A") (pinfunction "A_A") (pintype "passive"))
      (node (ref "X3") (pin "2") (pinfunction "S_2") (pintype "passive"))
    )
    (net (code "78") (name "VBAT_AU") (class "Default")
      (node (ref "AU") (pin "1") (pinfunction "1_1") (pintype "passive"))
      (node (ref "C1") (pin "+") (pinfunction "+_+") (pintype "passive"))
      (node (ref "C2") (pin "+") (pinfunction "+_+") (pintype "passive"))
      (node (ref "LEFT_STEPPER") (pin "V+") (pinfunction "V+_V+") (pintype "bidirectional"))
      (node (ref "OMRON1") (pin "3") (pinfunction "S_3") (pintype "passive"))
      (node (ref "OMRON2") (pin "3") (pinfunction "S_3") (pintype "passive"))
      (node (ref "OMRON3") (pin "3") (pinfunction "S_3") (pintype "passive"))
      (node (ref "OMRON4") (pin "3") (pinfunction "S_3") (pintype "passive"))
      (node (ref "RIGHT_STEPPER") (pin "V+") (pinfunction "V+_V+") (pintype "bidirectional"))
      (node (ref "SV1") (pin "1") (pinfunction "1_1") (pintype "passive"))
      (node (ref "SV2") (pin "1") (pinfunction "1_1") (pintype "passive"))
      (node (ref "V_AU") (pin "A") (pinfunction "A_A") (pintype "passive"))
    )
    (net (code "79") (name "unconnected-(LEFT_STEPPER-PadFAULT)") (class "Default")
      (node (ref "LEFT_STEPPER") (pin "FAULT") (pinfunction "FAULT_FAULT") (pintype "bidirectional"))
    )
    (net (code "80") (name "unconnected-(RIGHT_STEPPER-PadFAULT)") (class "Default")
      (node (ref "RIGHT_STEPPER") (pin "FAULT") (pinfunction "FAULT_FAULT") (pintype "bidirectional"))
    )
    (net (code "81") (name "unconnected-(SV1-Pad2)") (class "Default")
      (node (ref "SV1") (pin "2") (pinfunction "2_2") (pintype "passive"))
    )
    (net (code "82") (name "unconnected-(SV2-Pad2)") (class "Default")
      (node (ref "SV2") (pin "2") (pinfunction "2_2") (pintype "passive"))
    )
    (net (code "83") (name "unconnected-(U$1-Pad5V)") (class "Default")
      (node (ref "U$1") (pin "5V") (pinfunction "5V_5V") (pintype "bidirectional"))
    )
    (net (code "84") (name "unconnected-(U$1-Pad5V_A)") (class "Default")
      (node (ref "U$1") (pin "5V_A") (pinfunction "5V_A_5V_A") (pintype "bidirectional"))
    )
    (net (code "85") (name "unconnected-(U$1-Pad5V_B)") (class "Default")
      (node (ref "U$1") (pin "5V_B") (pinfunction "5V_B_5V_B") (pintype "bidirectional"))
    )
    (net (code "86") (name "unconnected-(U$1-Pad13)") (class "Default")
      (node (ref "U$1") (pin "13") (pinfunction "13_13") (pintype "bidirectional"))
    )
    (net (code "87") (name "unconnected-(U$1-Pad31)") (class "Default")
      (node (ref "U$1") (pin "31") (pinfunction "31_31") (pintype "bidirectional"))
    )
    (net (code "88") (name "unconnected-(U$1-Pad32)") (class "Default")
      (node (ref "U$1") (pin "32") (pinfunction "32_32") (pintype "bidirectional"))
    )
    (net (code "89") (name "unconnected-(U$1-Pad33)") (class "Default")
      (node (ref "U$1") (pin "33") (pinfunction "33_33") (pintype "bidirectional"))
    )
    (net (code "90") (name "unconnected-(U$1-Pad38)") (class "Default")
      (node (ref "U$1") (pin "38") (pinfunction "38_38") (pintype "bidirectional"))
    )
    (net (code "91") (name "unconnected-(U$1-Pad39)") (class "Default")
      (node (ref "U$1") (pin "39") (pinfunction "39_39") (pintype "bidirectional"))
    )
    (net (code "92") (name "unconnected-(U$1-Pad45)") (class "Default")
      (node (ref "U$1") (pin "45") (pinfunction "45_45") (pintype "bidirectional"))
    )
    (net (code "93") (name "unconnected-(U$1-Pad46)") (class "Default")
      (node (ref "U$1") (pin "46") (pinfunction "46_46") (pintype "bidirectional"))
    )
    (net (code "94") (name "unconnected-(U$1-PadA1)") (class "Default")
      (node (ref "U$1") (pin "A1") (pinfunction "A1_A1") (pintype "bidirectional"))
    )
    (net (code "95") (name "unconnected-(U$1-PadA2)") (class "Default")
      (node (ref "U$1") (pin "A2") (pinfunction "A2_A2") (pintype "bidirectional"))
    )
    (net (code "96") (name "unconnected-(U$1-PadA3)") (class "Default")
      (node (ref "U$1") (pin "A3") (pinfunction "A3_A3") (pintype "bidirectional"))
    )
    (net (code "97") (name "unconnected-(U$1-PadA4)") (class "Default")
      (node (ref "U$1") (pin "A4") (pinfunction "A4_A4") (pintype "bidirectional"))
    )
    (net (code "98") (name "unconnected-(U$1-PadA5)") (class "Default")
      (node (ref "U$1") (pin "A5") (pinfunction "A5_A5") (pintype "bidirectional"))
    )
    (net (code "99") (name "unconnected-(U$1-PadA6)") (class "Default")
      (node (ref "U$1") (pin "A6") (pinfunction "A6_A6") (pintype "bidirectional"))
    )
    (net (code "100") (name "unconnected-(U$1-PadA7)") (class "Default")
      (node (ref "U$1") (pin "A7") (pinfunction "A7_A7") (pintype "bidirectional"))
    )
    (net (code "101") (name "unconnected-(U$1-PadA8)") (class "Default")
      (node (ref "U$1") (pin "A8") (pinfunction "A8_A8") (pintype "bidirectional"))
    )
    (net (code "102") (name "unconnected-(U$1-PadA9)") (class "Default")
      (node (ref "U$1") (pin "A9") (pinfunction "A9_A9") (pintype "bidirectional"))
    )
    (net (code "103") (name "unconnected-(U$1-PadA10)") (class "Default")
      (node (ref "U$1") (pin "A10") (pinfunction "A10_A10") (pintype "bidirectional"))
    )
    (net (code "104") (name "unconnected-(U$1-PadA11)") (class "Default")
      (node (ref "U$1") (pin "A11") (pinfunction "A11_A11") (pintype "bidirectional"))
    )
    (net (code "105") (name "unconnected-(U$1-PadAREF)") (class "Default")
      (node (ref "U$1") (pin "AREF") (pinfunction "AREF_AREF") (pintype "bidirectional"))
    )
    (net (code "106") (name "unconnected-(U$1-PadCANRX)") (class "Default")
      (node (ref "U$1") (pin "CANRX") (pinfunction "CANRX_CANRX") (pintype "bidirectional"))
    )
    (net (code "107") (name "unconnected-(U$1-PadCANTX)") (class "Default")
      (node (ref "U$1") (pin "CANTX") (pinfunction "CANTX_CANTX") (pintype "bidirectional"))
    )
    (net (code "108") (name "unconnected-(U$1-PadDAC0)") (class "Default")
      (node (ref "U$1") (pin "DAC0") (pinfunction "DAC0_DAC0") (pintype "bidirectional"))
    )
    (net (code "109") (name "unconnected-(U$1-PadDAC1)") (class "Default")
      (node (ref "U$1") (pin "DAC1") (pinfunction "DAC1_DAC1") (pintype "bidirectional"))
    )
    (net (code "110") (name "unconnected-(U$1-PadGND1)") (class "Default")
      (node (ref "U$1") (pin "GND1") (pinfunction "GND1_GND1") (pintype "bidirectional"))
    )
    (net (code "111") (name "unconnected-(U$1-PadGND_A)") (class "Default")
      (node (ref "U$1") (pin "GND_A") (pinfunction "GND_A_GND_A") (pintype "bidirectional"))
    )
    (net (code "112") (name "unconnected-(U$1-PadGND_B)") (class "Default")
      (node (ref "U$1") (pin "GND_B") (pinfunction "GND_B_GND_B") (pintype "bidirectional"))
    )
    (net (code "113") (name "unconnected-(U$1-PadIOREF)") (class "Default")
      (node (ref "U$1") (pin "IOREF") (pinfunction "IOREF_IOREF") (pintype "bidirectional"))
    )
    (net (code "114") (name "unconnected-(U$1-PadNC)") (class "Default")
      (node (ref "U$1") (pin "NC") (pinfunction "NC_NC") (pintype "bidirectional"))
    )
    (net (code "115") (name "unconnected-(U$1-PadRX0)") (class "Default")
      (node (ref "U$1") (pin "RX0") (pinfunction "RX0_RX0") (pintype "bidirectional"))
    )
    (net (code "116") (name "unconnected-(U$1-PadRX1)") (class "Default")
      (node (ref "U$1") (pin "RX1") (pinfunction "RX1_RX1") (pintype "bidirectional"))
    )
    (net (code "117") (name "unconnected-(U$1-PadRX2)") (class "Default")
      (node (ref "U$1") (pin "RX2") (pinfunction "RX2_RX2") (pintype "bidirectional"))
    )
    (net (code "118") (name "unconnected-(U$1-PadRX3)") (class "Default")
      (node (ref "U$1") (pin "RX3") (pinfunction "RX3_RX3") (pintype "bidirectional"))
    )
    (net (code "119") (name "unconnected-(U$1-PadSCL)") (class "Default")
      (node (ref "U$1") (pin "SCL") (pinfunction "SCL_SCL") (pintype "bidirectional"))
    )
    (net (code "120") (name "unconnected-(U$1-PadSCL1)") (class "Default")
      (node (ref "U$1") (pin "SCL1") (pinfunction "SCL1_SCL1") (pintype "bidirectional"))
    )
    (net (code "121") (name "unconnected-(U$1-PadSDA)") (class "Default")
      (node (ref "U$1") (pin "SDA") (pinfunction "SDA_SDA") (pintype "bidirectional"))
    )
    (net (code "122") (name "unconnected-(U$1-PadSDA1)") (class "Default")
      (node (ref "U$1") (pin "SDA1") (pinfunction "SDA1_SDA1") (pintype "bidirectional"))
    )
    (net (code "123") (name "unconnected-(U$1-PadTX0)") (class "Default")
      (node (ref "U$1") (pin "TX0") (pinfunction "TX0_TX0") (pintype "bidirectional"))
    )
    (net (code "124") (name "unconnected-(U$1-PadTX1)") (class "Default")
      (node (ref "U$1") (pin "TX1") (pinfunction "TX1_TX1") (pintype "bidirectional"))
    )
    (net (code "125") (name "unconnected-(U$1-PadTX2)") (class "Default")
      (node (ref "U$1") (pin "TX2") (pinfunction "TX2_TX2") (pintype "bidirectional"))
    )
    (net (code "126") (name "unconnected-(U$1-PadTX3)") (class "Default")
      (node (ref "U$1") (pin "TX3") (pinfunction "TX3_TX3") (pintype "bidirectional"))
    )
  )
)
